# Card4to16_50mm.net
KiCad netlist of a schematic drawn in EAGLE
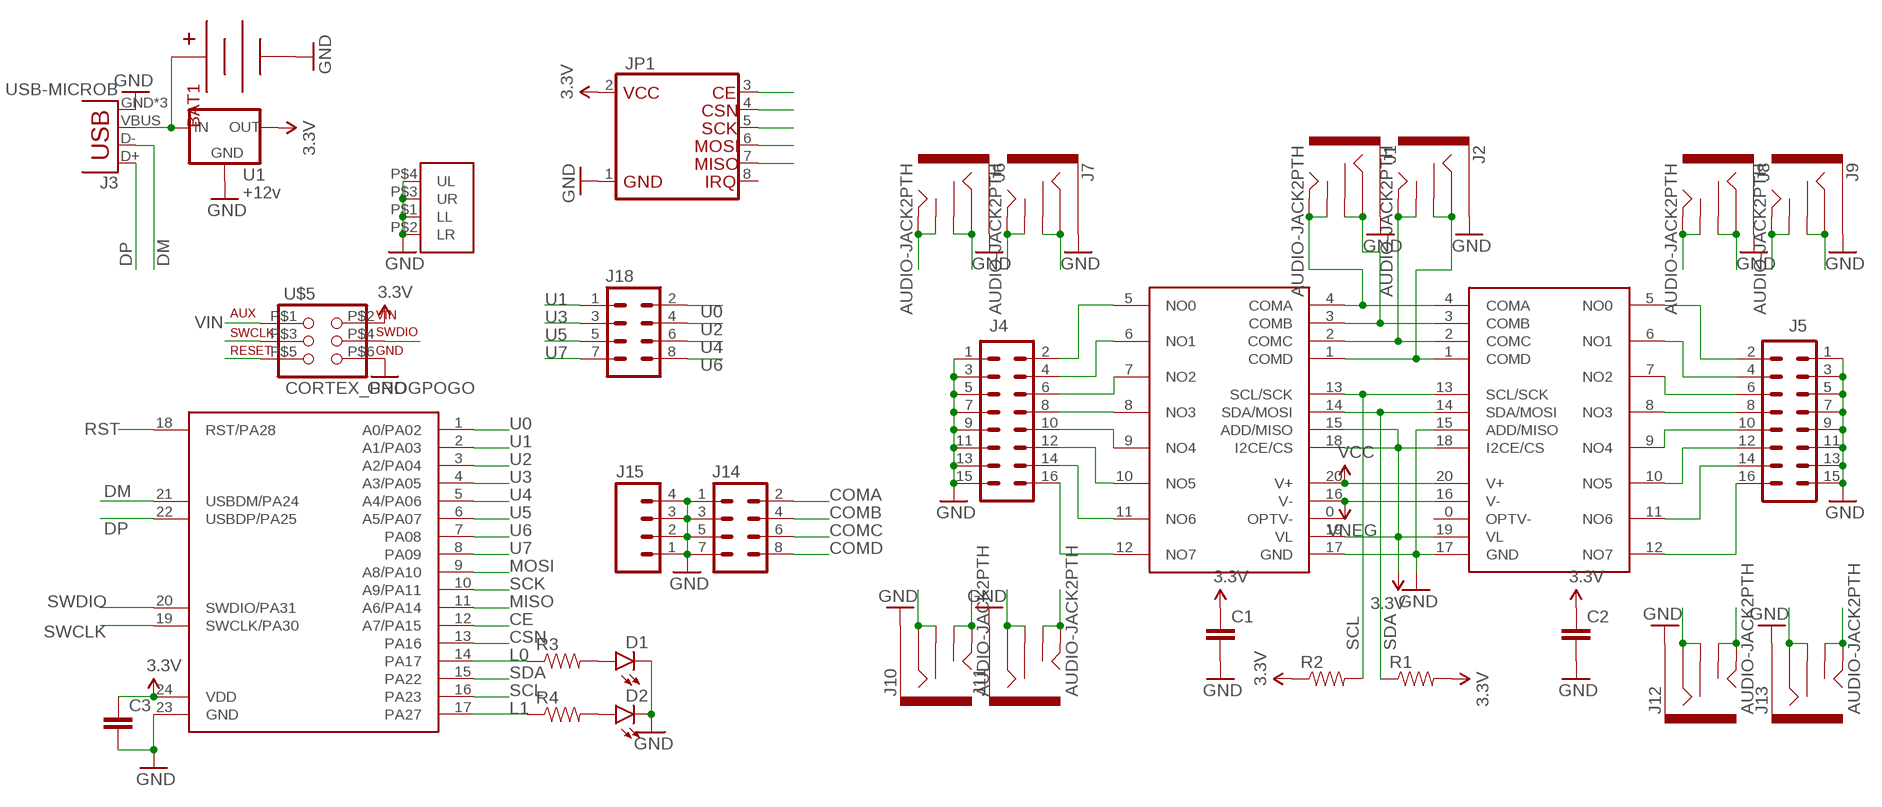
[diagram p0: schematic, sheet 1]

(export (version "E")
  (design (tool "Eeschema 10.0.6"))
  (components
    (comp (ref "BAT1")
      (value "9VHOLDERCLIPS")
      (footprint "eagle-import:BSPC9V")
      (libsource (lib "eagle-import") (part "9VHOLDERCLIPS"))
    )
    (comp (ref "C1")
      (value "CAP0805")
      (footprint "eagle-import:0805")
      (libsource (lib "eagle-import") (part "CAP0805"))
    )
    (comp (ref "C2")
      (value "CAP0805")
      (footprint "eagle-import:0805")
      (libsource (lib "eagle-import") (part "CAP0805"))
    )
    (comp (ref "C3")
      (value "CAP0805")
      (footprint "eagle-import:0805")
      (libsource (lib "eagle-import") (part "CAP0805"))
    )
    (comp (ref "D1")
      (value "LED1206")
      (footprint "eagle-import:LED-1206")
      (libsource (lib "eagle-import") (part "LED1206"))
    )
    (comp (ref "D2")
      (value "LED1206")
      (footprint "eagle-import:LED-1206")
      (libsource (lib "eagle-import") (part "LED1206"))
    )
    (comp (ref "J1")
      (value "AUDIO-JACK2PTH")
      (footprint "eagle-import:AUDIO-JACK")
      (libsource (lib "eagle-import") (part "AUDIO-JACK2PTH"))
    )
    (comp (ref "J2")
      (value "AUDIO-JACK2PTH")
      (footprint "eagle-import:AUDIO-JACK")
      (libsource (lib "eagle-import") (part "AUDIO-JACK2PTH"))
    )
    (comp (ref "J3")
      (value "USB-MICROB")
      (footprint "eagle-import:USB-MICROB")
      (libsource (lib "eagle-import") (part "USB-MICROB"))
    )
    (comp (ref "J4")
      (value "M08X2")
      (footprint "eagle-import:2X8")
      (libsource (lib "eagle-import") (part "M08X2"))
    )
    (comp (ref "J5")
      (value "M08X2")
      (footprint "eagle-import:2X8")
      (libsource (lib "eagle-import") (part "M08X2"))
    )
    (comp (ref "J6")
      (value "AUDIO-JACK2PTH")
      (footprint "eagle-import:AUDIO-JACK")
      (libsource (lib "eagle-import") (part "AUDIO-JACK2PTH"))
    )
    (comp (ref "J7")
      (value "AUDIO-JACK2PTH")
      (footprint "eagle-import:AUDIO-JACK")
      (libsource (lib "eagle-import") (part "AUDIO-JACK2PTH"))
    )
    (comp (ref "J8")
      (value "AUDIO-JACK2PTH")
      (footprint "eagle-import:AUDIO-JACK")
      (libsource (lib "eagle-import") (part "AUDIO-JACK2PTH"))
    )
    (comp (ref "J9")
      (value "AUDIO-JACK2PTH")
      (footprint "eagle-import:AUDIO-JACK")
      (libsource (lib "eagle-import") (part "AUDIO-JACK2PTH"))
    )
    (comp (ref "J10")
      (value "AUDIO-JACK2PTH")
      (footprint "eagle-import:AUDIO-JACK")
      (libsource (lib "eagle-import") (part "AUDIO-JACK2PTH"))
    )
    (comp (ref "J11")
      (value "AUDIO-JACK2PTH")
      (footprint "eagle-import:AUDIO-JACK")
      (libsource (lib "eagle-import") (part "AUDIO-JACK2PTH"))
    )
    (comp (ref "J12")
      (value "AUDIO-JACK2PTH")
      (footprint "eagle-import:AUDIO-JACK")
      (libsource (lib "eagle-import") (part "AUDIO-JACK2PTH"))
    )
    (comp (ref "J13")
      (value "AUDIO-JACK2PTH")
      (footprint "eagle-import:AUDIO-JACK")
      (libsource (lib "eagle-import") (part "AUDIO-JACK2PTH"))
    )
    (comp (ref "J14")
      (value "M04X2")
      (footprint "eagle-import:2X4")
      (libsource (lib "eagle-import") (part "M04X2"))
    )
    (comp (ref "J15")
      (value "M04PTH")
      (footprint "eagle-import:1X04")
      (libsource (lib "eagle-import") (part "M04PTH"))
    )
    (comp (ref "J18")
      (value "M04X2")
      (footprint "eagle-import:2X4")
      (libsource (lib "eagle-import") (part "M04X2"))
    )
    (comp (ref "JP1")
      (value "NRF24L01+SHORT_FLUSH")
      (footprint "eagle-import:NRF24L01SHORT")
      (libsource (lib "eagle-import") (part "NRF24L01+SHORT_FLUSH"))
    )
    (comp (ref "R1")
      (value "RESISTOR0603-RES")
      (footprint "eagle-import:0603-RES")
      (libsource (lib "eagle-import") (part "RESISTOR0603-RES"))
    )
    (comp (ref "R2")
      (value "RESISTOR0603-RES")
      (footprint "eagle-import:0603-RES")
      (libsource (lib "eagle-import") (part "RESISTOR0603-RES"))
    )
    (comp (ref "R3")
      (value "RESISTOR0603-RES")
      (footprint "eagle-import:0603-RES")
      (libsource (lib "eagle-import") (part "RESISTOR0603-RES"))
    )
    (comp (ref "R4")
      (value "RESISTOR0603-RES")
      (footprint "eagle-import:0603-RES")
      (libsource (lib "eagle-import") (part "RESISTOR0603-RES"))
    )
    (comp (ref "U$1")
      (value "MAX14724ETP+QFN")
      (footprint "eagle-import:QFN20_4X4")
      (libsource (lib "eagle-import") (part "MAX14724ETP+QFN"))
    )
    (comp (ref "U$2")
      (value "MAX14724ETP+QFN")
      (footprint "eagle-import:QFN20_4X4")
      (libsource (lib "eagle-import") (part "MAX14724ETP+QFN"))
    )
    (comp (ref "U$3")
      (value "ATSAMD11D14A-M")
      (footprint "eagle-import:QFN24_4X4")
      (libsource (lib "eagle-import") (part "ATSAMD11D14A-M"))
    )
    (comp (ref "U$4")
      (value "CARD_HOLES50MM")
      (footprint "eagle-import:IEC-7810_ID-1_HOLES_50MM")
      (libsource (lib "eagle-import") (part "CARD_HOLES50MM"))
    )
    (comp (ref "U$5")
      (value "CORTEX_PROGPOGO")
      (footprint "eagle-import:2X3_MAX")
      (libsource (lib "eagle-import") (part "CORTEX_PROGPOGO"))
    )
    (comp (ref "U1")
      (value "+12v")
      (footprint "eagle-import:TO-252")
      (libsource (lib "eagle-import") (part "V_REG_78XX7812"))
    )
  )
  (nets
    (net (code "1") (name "/CE") (class "Default")
      (node (ref "JP1") (pin "3") (pinfunction "CE_3") (pintype "passive"))
      (node (ref "U$3") (pin "12") (pinfunction "A7/PA15_12") (pintype "bidirectional"))
    )
    (net (code "2") (name "/COMA") (class "Default")
      (node (ref "J1") (pin "TIP") (pinfunction "TIP_TIP") (pintype "bidirectional"))
      (node (ref "J1") (pin "TSH") (pinfunction "TSH_TSH") (pintype "bidirectional"))
      (node (ref "J14") (pin "2") (pinfunction "2_2") (pintype "passive"))
      (node (ref "U$1") (pin "4") (pinfunction "COMA_4") (pintype "bidirectional"))
      (node (ref "U$2") (pin "4") (pinfunction "COMA_4") (pintype "bidirectional"))
    )
    (net (code "3") (name "/COMB") (class "Default")
      (node (ref "J1") (pin "RING") (pinfunction "RING_RING") (pintype "bidirectional"))
      (node (ref "J1") (pin "RSH") (pinfunction "RSH_RSH") (pintype "bidirectional"))
      (node (ref "J14") (pin "4") (pinfunction "4_4") (pintype "passive"))
      (node (ref "U$1") (pin "3") (pinfunction "COMB_3") (pintype "bidirectional"))
      (node (ref "U$2") (pin "3") (pinfunction "COMB_3") (pintype "bidirectional"))
    )
    (net (code "4") (name "/COMC") (class "Default")
      (node (ref "J14") (pin "6") (pinfunction "6_6") (pintype "passive"))
      (node (ref "J2") (pin "TIP") (pinfunction "TIP_TIP") (pintype "bidirectional"))
      (node (ref "J2") (pin "TSH") (pinfunction "TSH_TSH") (pintype "bidirectional"))
      (node (ref "U$1") (pin "2") (pinfunction "COMC_2") (pintype "bidirectional"))
      (node (ref "U$2") (pin "2") (pinfunction "COMC_2") (pintype "bidirectional"))
    )
    (net (code "5") (name "/COMD") (class "Default")
      (node (ref "J14") (pin "8") (pinfunction "8_8") (pintype "passive"))
      (node (ref "J2") (pin "RING") (pinfunction "RING_RING") (pintype "bidirectional"))
      (node (ref "J2") (pin "RSH") (pinfunction "RSH_RSH") (pintype "bidirectional"))
      (node (ref "U$1") (pin "1") (pinfunction "COMD_1") (pintype "bidirectional"))
      (node (ref "U$2") (pin "1") (pinfunction "COMD_1") (pintype "bidirectional"))
    )
    (net (code "6") (name "/CSN") (class "Default")
      (node (ref "JP1") (pin "4") (pinfunction "CSN_4") (pintype "passive"))
      (node (ref "U$3") (pin "13") (pinfunction "PA16_13") (pintype "bidirectional"))
    )
    (net (code "7") (name "/DM") (class "Default")
      (node (ref "J3") (pin "D-") (pinfunction "D-_D-") (pintype "bidirectional"))
      (node (ref "U$3") (pin "21") (pinfunction "USBDM/PA24_21") (pintype "bidirectional"))
    )
    (net (code "8") (name "/DP") (class "Default")
      (node (ref "J3") (pin "D+") (pinfunction "D+_D+") (pintype "bidirectional"))
      (node (ref "U$3") (pin "22") (pinfunction "USBDP/PA25_22") (pintype "bidirectional"))
    )
    (net (code "9") (name "/L0") (class "Default")
      (node (ref "R3") (pin "1") (pinfunction "1_1") (pintype "passive"))
      (node (ref "U$3") (pin "14") (pinfunction "PA17_14") (pintype "bidirectional"))
    )
    (net (code "10") (name "/L1") (class "Default")
      (node (ref "R4") (pin "1") (pinfunction "1_1") (pintype "passive"))
      (node (ref "U$3") (pin "17") (pinfunction "PA27_17") (pintype "bidirectional"))
    )
    (net (code "11") (name "/MISO") (class "Default")
      (node (ref "JP1") (pin "7") (pinfunction "MISO_7") (pintype "passive"))
      (node (ref "U$3") (pin "11") (pinfunction "A6/PA14_11") (pintype "bidirectional"))
    )
    (net (code "12") (name "/MOSI") (class "Default")
      (node (ref "JP1") (pin "6") (pinfunction "MOSI_6") (pintype "passive"))
      (node (ref "U$3") (pin "9") (pinfunction "A8/PA10_9") (pintype "bidirectional"))
    )
    (net (code "13") (name "/OUT1") (class "Default")
      (node (ref "J10") (pin "RING") (pinfunction "RING_RING") (pintype "bidirectional"))
      (node (ref "J10") (pin "RSH") (pinfunction "RSH_RSH") (pintype "bidirectional"))
      (node (ref "J4") (pin "2") (pinfunction "2_2") (pintype "passive"))
      (node (ref "U$1") (pin "5") (pinfunction "NO0_5") (pintype "bidirectional"))
    )
    (net (code "14") (name "/OUT2") (class "Default")
      (node (ref "J10") (pin "TIP") (pinfunction "TIP_TIP") (pintype "bidirectional"))
      (node (ref "J10") (pin "TSH") (pinfunction "TSH_TSH") (pintype "bidirectional"))
      (node (ref "J4") (pin "4") (pinfunction "4_4") (pintype "passive"))
      (node (ref "U$1") (pin "6") (pinfunction "NO1_6") (pintype "bidirectional"))
    )
    (net (code "15") (name "/OUT3") (class "Default")
      (node (ref "J11") (pin "RING") (pinfunction "RING_RING") (pintype "bidirectional"))
      (node (ref "J11") (pin "RSH") (pinfunction "RSH_RSH") (pintype "bidirectional"))
      (node (ref "J4") (pin "6") (pinfunction "6_6") (pintype "passive"))
      (node (ref "U$1") (pin "7") (pinfunction "NO2_7") (pintype "bidirectional"))
    )
    (net (code "16") (name "/OUT4") (class "Default")
      (node (ref "J11") (pin "TIP") (pinfunction "TIP_TIP") (pintype "bidirectional"))
      (node (ref "J11") (pin "TSH") (pinfunction "TSH_TSH") (pintype "bidirectional"))
      (node (ref "J4") (pin "8") (pinfunction "8_8") (pintype "passive"))
      (node (ref "U$1") (pin "8") (pinfunction "NO3_8") (pintype "bidirectional"))
    )
    (net (code "17") (name "/OUT5") (class "Default")
      (node (ref "J12") (pin "RING") (pinfunction "RING_RING") (pintype "bidirectional"))
      (node (ref "J12") (pin "RSH") (pinfunction "RSH_RSH") (pintype "bidirectional"))
      (node (ref "J4") (pin "10") (pinfunction "10_10") (pintype "passive"))
      (node (ref "U$1") (pin "9") (pinfunction "NO4_9") (pintype "bidirectional"))
    )
    (net (code "18") (name "/OUT6") (class "Default")
      (node (ref "J12") (pin "TIP") (pinfunction "TIP_TIP") (pintype "bidirectional"))
      (node (ref "J12") (pin "TSH") (pinfunction "TSH_TSH") (pintype "bidirectional"))
      (node (ref "J4") (pin "12") (pinfunction "12_12") (pintype "passive"))
      (node (ref "U$1") (pin "10") (pinfunction "NO5_10") (pintype "bidirectional"))
    )
    (net (code "19") (name "/OUT7") (class "Default")
      (node (ref "J13") (pin "RING") (pinfunction "RING_RING") (pintype "bidirectional"))
      (node (ref "J13") (pin "RSH") (pinfunction "RSH_RSH") (pintype "bidirectional"))
      (node (ref "J4") (pin "14") (pinfunction "14_14") (pintype "passive"))
      (node (ref "U$1") (pin "11") (pinfunction "NO6_11") (pintype "bidirectional"))
    )
    (net (code "20") (name "/OUT8") (class "Default")
      (node (ref "J13") (pin "TIP") (pinfunction "TIP_TIP") (pintype "bidirectional"))
      (node (ref "J13") (pin "TSH") (pinfunction "TSH_TSH") (pintype "bidirectional"))
      (node (ref "J4") (pin "16") (pinfunction "16_16") (pintype "passive"))
      (node (ref "U$1") (pin "12") (pinfunction "NO7_12") (pintype "bidirectional"))
    )
    (net (code "21") (name "/OUT9") (class "Default")
      (node (ref "J5") (pin "2") (pinfunction "2_2") (pintype "passive"))
      (node (ref "J6") (pin "RING") (pinfunction "RING_RING") (pintype "bidirectional"))
      (node (ref "J6") (pin "RSH") (pinfunction "RSH_RSH") (pintype "bidirectional"))
      (node (ref "U$2") (pin "5") (pinfunction "NO0_5") (pintype "bidirectional"))
    )
    (net (code "22") (name "/OUT10") (class "Default")
      (node (ref "J5") (pin "4") (pinfunction "4_4") (pintype "passive"))
      (node (ref "J6") (pin "TIP") (pinfunction "TIP_TIP") (pintype "bidirectional"))
      (node (ref "J6") (pin "TSH") (pinfunction "TSH_TSH") (pintype "bidirectional"))
      (node (ref "U$2") (pin "6") (pinfunction "NO1_6") (pintype "bidirectional"))
    )
    (net (code "23") (name "/OUT11") (class "Default")
      (node (ref "J5") (pin "6") (pinfunction "6_6") (pintype "passive"))
      (node (ref "J7") (pin "RING") (pinfunction "RING_RING") (pintype "bidirectional"))
      (node (ref "J7") (pin "RSH") (pinfunction "RSH_RSH") (pintype "bidirectional"))
      (node (ref "U$2") (pin "7") (pinfunction "NO2_7") (pintype "bidirectional"))
    )
    (net (code "24") (name "/OUT12") (class "Default")
      (node (ref "J5") (pin "8") (pinfunction "8_8") (pintype "passive"))
      (node (ref "J7") (pin "TIP") (pinfunction "TIP_TIP") (pintype "bidirectional"))
      (node (ref "J7") (pin "TSH") (pinfunction "TSH_TSH") (pintype "bidirectional"))
      (node (ref "U$2") (pin "8") (pinfunction "NO3_8") (pintype "bidirectional"))
    )
    (net (code "25") (name "/OUT13") (class "Default")
      (node (ref "J5") (pin "10") (pinfunction "10_10") (pintype "passive"))
      (node (ref "J8") (pin "RING") (pinfunction "RING_RING") (pintype "bidirectional"))
      (node (ref "J8") (pin "RSH") (pinfunction "RSH_RSH") (pintype "bidirectional"))
      (node (ref "U$2") (pin "9") (pinfunction "NO4_9") (pintype "bidirectional"))
    )
    (net (code "26") (name "/OUT14") (class "Default")
      (node (ref "J5") (pin "12") (pinfunction "12_12") (pintype "passive"))
      (node (ref "J8") (pin "TIP") (pinfunction "TIP_TIP") (pintype "bidirectional"))
      (node (ref "J8") (pin "TSH") (pinfunction "TSH_TSH") (pintype "bidirectional"))
      (node (ref "U$2") (pin "10") (pinfunction "NO5_10") (pintype "bidirectional"))
    )
    (net (code "27") (name "/OUT15") (class "Default")
      (node (ref "J5") (pin "14") (pinfunction "14_14") (pintype "passive"))
      (node (ref "J9") (pin "RING") (pinfunction "RING_RING") (pintype "bidirectional"))
      (node (ref "J9") (pin "RSH") (pinfunction "RSH_RSH") (pintype "bidirectional"))
      (node (ref "U$2") (pin "11") (pinfunction "NO6_11") (pintype "bidirectional"))
    )
    (net (code "28") (name "/OUT16") (class "Default")
      (node (ref "J5") (pin "16") (pinfunction "16_16") (pintype "passive"))
      (node (ref "J9") (pin "TIP") (pinfunction "TIP_TIP") (pintype "bidirectional"))
      (node (ref "J9") (pin "TSH") (pinfunction "TSH_TSH") (pintype "bidirectional"))
      (node (ref "U$2") (pin "12") (pinfunction "NO7_12") (pintype "bidirectional"))
    )
    (net (code "29") (name "/RST") (class "Default")
      (node (ref "U$3") (pin "18") (pinfunction "RST/PA28_18") (pintype "bidirectional"))
      (node (ref "U$5") (pin "P$5") (pinfunction "RST_P$5") (pintype "passive"))
    )
    (net (code "30") (name "/SCK") (class "Default")
      (node (ref "JP1") (pin "5") (pinfunction "SCK_5") (pintype "passive"))
      (node (ref "U$3") (pin "10") (pinfunction "A9/PA11_10") (pintype "bidirectional"))
    )
    (net (code "31") (name "/SCL") (class "Default")
      (node (ref "R2") (pin "2") (pinfunction "2_2") (pintype "passive"))
      (node (ref "U$1") (pin "13") (pinfunction "SCL/SCK_13") (pintype "bidirectional"))
      (node (ref "U$2") (pin "13") (pinfunction "SCL/SCK_13") (pintype "bidirectional"))
      (node (ref "U$3") (pin "16") (pinfunction "PA23_16") (pintype "bidirectional"))
    )
    (net (code "32") (name "/SDA") (class "Default")
      (node (ref "R1") (pin "1") (pinfunction "1_1") (pintype "passive"))
      (node (ref "U$1") (pin "14") (pinfunction "SDA/MOSI_14") (pintype "bidirectional"))
      (node (ref "U$2") (pin "14") (pinfunction "SDA/MOSI_14") (pintype "bidirectional"))
      (node (ref "U$3") (pin "15") (pinfunction "PA22_15") (pintype "bidirectional"))
    )
    (net (code "33") (name "/SWCLK") (class "Default")
      (node (ref "U$3") (pin "19") (pinfunction "SWCLK/PA30_19") (pintype "bidirectional"))
      (node (ref "U$5") (pin "P$3") (pinfunction "SWCLK_P$3") (pintype "passive"))
    )
    (net (code "34") (name "/SWDIO") (class "Default")
      (node (ref "U$3") (pin "20") (pinfunction "SWDIO/PA31_20") (pintype "bidirectional"))
      (node (ref "U$5") (pin "P$4") (pinfunction "SWDIO_P$4") (pintype "passive"))
    )
    (net (code "35") (name "/U0") (class "Default")
      (node (ref "J18") (pin "2") (pinfunction "2_2") (pintype "passive"))
      (node (ref "U$3") (pin "1") (pinfunction "A0/PA02_1") (pintype "bidirectional"))
    )
    (net (code "36") (name "/U1") (class "Default")
      (node (ref "J18") (pin "1") (pinfunction "1_1") (pintype "passive"))
      (node (ref "U$3") (pin "2") (pinfunction "A1/PA03_2") (pintype "bidirectional"))
    )
    (net (code "37") (name "/U2") (class "Default")
      (node (ref "J18") (pin "4") (pinfunction "4_4") (pintype "passive"))
      (node (ref "U$3") (pin "3") (pinfunction "A2/PA04_3") (pintype "bidirectional"))
    )
    (net (code "38") (name "/U3") (class "Default")
      (node (ref "J18") (pin "3") (pinfunction "3_3") (pintype "passive"))
      (node (ref "U$3") (pin "4") (pinfunction "A3/PA05_4") (pintype "bidirectional"))
    )
    (net (code "39") (name "/U4") (class "Default")
      (node (ref "J18") (pin "6") (pinfunction "6_6") (pintype "passive"))
      (node (ref "U$3") (pin "5") (pinfunction "A4/PA06_5") (pintype "bidirectional"))
    )
    (net (code "40") (name "/U5") (class "Default")
      (node (ref "J18") (pin "5") (pinfunction "5_5") (pintype "passive"))
      (node (ref "U$3") (pin "6") (pinfunction "A5/PA07_6") (pintype "bidirectional"))
    )
    (net (code "41") (name "/U6") (class "Default")
      (node (ref "J18") (pin "8") (pinfunction "8_8") (pintype "passive"))
      (node (ref "U$3") (pin "7") (pinfunction "PA08_7") (pintype "bidirectional"))
    )
    (net (code "42") (name "/U7") (class "Default")
      (node (ref "J18") (pin "7") (pinfunction "7_7") (pintype "passive"))
      (node (ref "U$3") (pin "8") (pinfunction "PA09_8") (pintype "bidirectional"))
    )
    (net (code "43") (name "/VIN") (class "Default")
      (node (ref "BAT1") (pin "P$4") (pinfunction "V+_P$4") (pintype "bidirectional"))
      (node (ref "BAT1") (pin "P$5") (pinfunction "V+_P$5") (pintype "bidirectional"))
      (node (ref "BAT1") (pin "P$6") (pinfunction "V+_P$6") (pintype "bidirectional"))
      (node (ref "J3") (pin "VBUS") (pinfunction "VBUS_VBUS") (pintype "bidirectional"))
      (node (ref "U$5") (pin "P$1") (pinfunction "AUX_P$1") (pintype "passive"))
      (node (ref "U1") (pin "1") (pinfunction "IN_1") (pintype "input"))
    )
    (net (code "44") (name "3.3V") (class "Default")
      (node (ref "C1") (pin "1") (pinfunction "1_1") (pintype "passive"))
      (node (ref "C2") (pin "1") (pinfunction "1_1") (pintype "passive"))
      (node (ref "C3") (pin "1") (pinfunction "1_1") (pintype "passive"))
      (node (ref "JP1") (pin "2") (pinfunction "VCC_2") (pintype "passive"))
      (node (ref "R1") (pin "2") (pinfunction "2_2") (pintype "passive"))
      (node (ref "R2") (pin "1") (pinfunction "1_1") (pintype "passive"))
      (node (ref "U$1") (pin "15") (pinfunction "ADD/MISO_15") (pintype "bidirectional"))
      (node (ref "U$1") (pin "18") (pinfunction "I2CE/CS_18") (pintype "bidirectional"))
      (node (ref "U$1") (pin "19") (pinfunction "VL_19") (pintype "bidirectional"))
      (node (ref "U$2") (pin "18") (pinfunction "I2CE/CS_18") (pintype "bidirectional"))
      (node (ref "U$2") (pin "19") (pinfunction "VL_19") (pintype "bidirectional"))
      (node (ref "U$3") (pin "24") (pinfunction "VDD_24") (pintype "bidirectional"))
      (node (ref "U$5") (pin "P$2") (pinfunction "VIN_P$2") (pintype "passive"))
      (node (ref "U1") (pin "2") (pinfunction "OUT_2") (pintype "passive"))
    )
    (net (code "45") (name "GND") (class "Default")
      (node (ref "BAT1") (pin "P$1") (pinfunction "V-_P$1") (pintype "bidirectional"))
      (node (ref "BAT1") (pin "P$2") (pinfunction "V-_P$2") (pintype "bidirectional"))
      (node (ref "BAT1") (pin "P$3") (pinfunction "V-_P$3") (pintype "bidirectional"))
      (node (ref "C1") (pin "2") (pinfunction "2_2") (pintype "passive"))
      (node (ref "C2") (pin "2") (pinfunction "2_2") (pintype "passive"))
      (node (ref "C3") (pin "2") (pinfunction "2_2") (pintype "passive"))
      (node (ref "D1") (pin "C") (pinfunction "C_C") (pintype "passive"))
      (node (ref "D2") (pin "C") (pinfunction "C_C") (pintype "passive"))
      (node (ref "J1") (pin "SLEEVE") (pinfunction "SLEEVE_SLEEVE") (pintype "bidirectional"))
      (node (ref "J10") (pin "SLEEVE") (pinfunction "SLEEVE_SLEEVE") (pintype "bidirectional"))
      (node (ref "J11") (pin "SLEEVE") (pinfunction "SLEEVE_SLEEVE") (pintype "bidirectional"))
      (node (ref "J12") (pin "SLEEVE") (pinfunction "SLEEVE_SLEEVE") (pintype "bidirectional"))
      (node (ref "J13") (pin "SLEEVE") (pinfunction "SLEEVE_SLEEVE") (pintype "bidirectional"))
      (node (ref "J14") (pin "1") (pinfunction "1_1") (pintype "passive"))
      (node (ref "J14") (pin "3") (pinfunction "3_3") (pintype "passive"))
      (node (ref "J14") (pin "5") (pinfunction "5_5") (pintype "passive"))
      (node (ref "J14") (pin "7") (pinfunction "7_7") (pintype "passive"))
      (node (ref "J15") (pin "1") (pinfunction "1_1") (pintype "passive"))
      (node (ref "J15") (pin "2") (pinfunction "2_2") (pintype "passive"))
      (node (ref "J15") (pin "3") (pinfunction "3_3") (pintype "passive"))
      (node (ref "J15") (pin "4") (pinfunction "4_4") (pintype "passive"))
      (node (ref "J2") (pin "SLEEVE") (pinfunction "SLEEVE_SLEEVE") (pintype "bidirectional"))
      (node (ref "J3") (pin "GND") (pinfunction "GND_GND") (pintype "bidirectional"))
      (node (ref "J3") (pin "MT1") (pinfunction "GND_MT1") (pintype "bidirectional"))
      (node (ref "J3") (pin "MT2") (pinfunction "GND_MT2") (pintype "bidirectional"))
      (node (ref "J4") (pin "1") (pinfunction "1_1") (pintype "passive"))
      (node (ref "J4") (pin "11") (pinfunction "11_11") (pintype "passive"))
      (node (ref "J4") (pin "13") (pinfunction "13_13") (pintype "passive"))
      (node (ref "J4") (pin "15") (pinfunction "15_15") (pintype "passive"))
      (node (ref "J4") (pin "3") (pinfunction "3_3") (pintype "passive"))
      (node (ref "J4") (pin "5") (pinfunction "5_5") (pintype "passive"))
      (node (ref "J4") (pin "7") (pinfunction "7_7") (pintype "passive"))
      (node (ref "J4") (pin "9") (pinfunction "9_9") (pintype "passive"))
      (node (ref "J5") (pin "1") (pinfunction "1_1") (pintype "passive"))
      (node (ref "J5") (pin "11") (pinfunction "11_11") (pintype "passive"))
      (node (ref "J5") (pin "13") (pinfunction "13_13") (pintype "passive"))
      (node (ref "J5") (pin "15") (pinfunction "15_15") (pintype "passive"))
      (node (ref "J5") (pin "3") (pinfunction "3_3") (pintype "passive"))
      (node (ref "J5") (pin "5") (pinfunction "5_5") (pintype "passive"))
      (node (ref "J5") (pin "7") (pinfunction "7_7") (pintype "passive"))
      (node (ref "J5") (pin "9") (pinfunction "9_9") (pintype "passive"))
      (node (ref "J6") (pin "SLEEVE") (pinfunction "SLEEVE_SLEEVE") (pintype "bidirectional"))
      (node (ref "J7") (pin "SLEEVE") (pinfunction "SLEEVE_SLEEVE") (pintype "bidirectional"))
      (node (ref "J8") (pin "SLEEVE") (pinfunction "SLEEVE_SLEEVE") (pintype "bidirectional"))
      (node (ref "J9") (pin "SLEEVE") (pinfunction "SLEEVE_SLEEVE") (pintype "bidirectional"))
      (node (ref "JP1") (pin "1") (pinfunction "GND_1") (pintype "passive"))
      (node (ref "U$1") (pin "17") (pinfunction "GND_17") (pintype "bidirectional"))
      (node (ref "U$2") (pin "15") (pinfunction "ADD/MISO_15") (pintype "bidirectional"))
      (node (ref "U$2") (pin "17") (pinfunction "GND_17") (pintype "bidirectional"))
      (node (ref "U$3") (pin "23") (pinfunction "GND_23") (pintype "bidirectional"))
      (node (ref "U$4") (pin "P$1") (pinfunction "LL_P$1") (pintype "bidirectional"))
      (node (ref "U$4") (pin "P$2") (pinfunction "LR_P$2") (pintype "bidirectional"))
      (node (ref "U$4") (pin "P$3") (pinfunction "UR_P$3") (pintype "bidirectional"))
      (node (ref "U$4") (pin "P$4") (pinfunction "UL_P$4") (pintype "bidirectional"))
      (node (ref "U$5") (pin "P$6") (pinfunction "GND_P$6") (pintype "passive"))
      (node (ref "U1") (pin "3") (pinfunction "GND_3") (pintype "input"))
    )
    (net (code "46") (name "Net-(D1-PadA)") (class "Default")
      (node (ref "D1") (pin "A") (pinfunction "A_A") (pintype "passive"))
      (node (ref "R3") (pin "2") (pinfunction "2_2") (pintype "passive"))
    )
    (net (code "47") (name "Net-(D2-PadA)") (class "Default")
      (node (ref "D2") (pin "A") (pinfunction "A_A") (pintype "passive"))
      (node (ref "R4") (pin "2") (pinfunction "2_2") (pintype "passive"))
    )
    (net (code "48") (name "VCC") (class "Default")
      (node (ref "U$1") (pin "20") (pinfunction "V+_20") (pintype "bidirectional"))
      (node (ref "U$2") (pin "20") (pinfunction "V+_20") (pintype "bidirectional"))
    )
    (net (code "49") (name "VNEG") (class "Default")
      (node (ref "U$1") (pin "16") (pinfunction "V-_16") (pintype "bidirectional"))
      (node (ref "U$2") (pin "16") (pinfunction "V-_16") (pintype "bidirectional"))
    )
    (net (code "50") (name "unconnected-(JP1-IRQ-Pad8)") (class "Default")
      (node (ref "JP1") (pin "8") (pinfunction "IRQ_8") (pintype "passive"))
    )
    (net (code "51") (name "unconnected-(U$1-OPTV--Pad0)") (class "Default")
      (node (ref "U$1") (pin "0") (pinfunction "OPTV-_0") (pintype "bidirectional"))
    )
    (net (code "52") (name "unconnected-(U$2-OPTV--Pad0)") (class "Default")
      (node (ref "U$2") (pin "0") (pinfunction "OPTV-_0") (pintype "bidirectional"))
    )
  )
)
